# 03-LcdSegment.net
KiCad netlist of a schematic drawn in Altium Designer
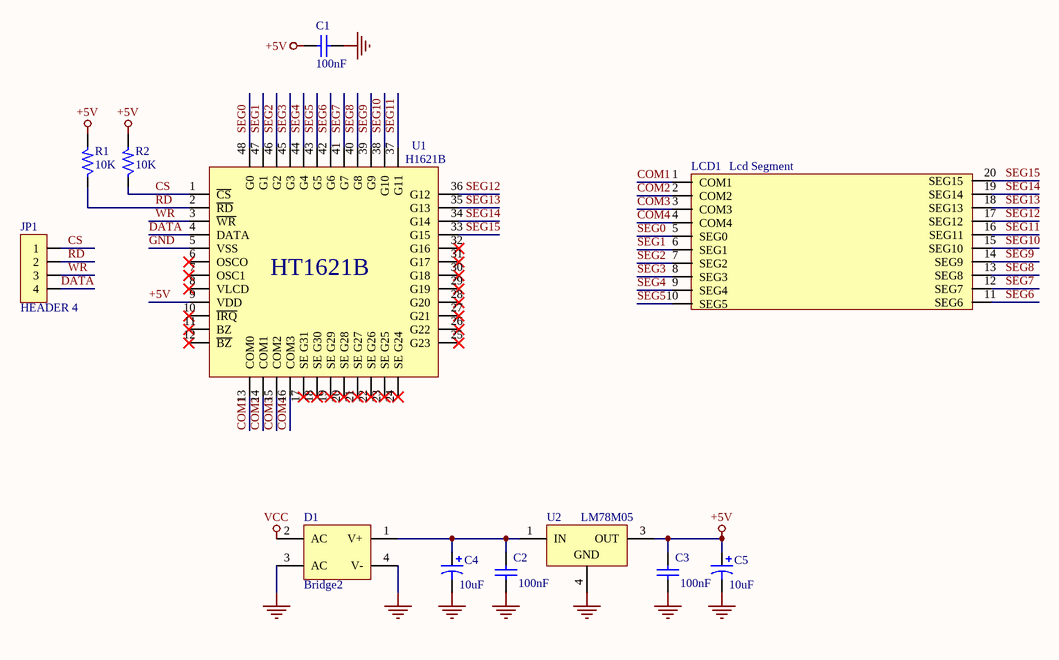
[diagram p0: 03-LcdSegment.SchDoc]

(export (version "E")
  (design (tool "Eeschema 10.0.6"))
  (components
    (comp (ref "C1")
      (value "100nF")
      (footprint "RAD-0.3")
      (description "Capacitor")
      (fields (field (name "Comment") "104") (field (name "PUBLISHER") "Altium Limited"))
      (libsource (lib "Miscellaneous Devices") (part "Cap"))
    )
    (comp (ref "C2")
      (value "100nF")
      (footprint "RAD-0.3")
      (description "Capacitor")
      (fields (field (name "Comment") "104") (field (name "PUBLISHER") "Altium Limited"))
      (libsource (lib "Miscellaneous Devices") (part "Cap"))
    )
    (comp (ref "C3")
      (value "100nF")
      (footprint "RAD-0.3")
      (description "Capacitor")
      (fields (field (name "Comment") "104") (field (name "PUBLISHER") "Altium Limited"))
      (libsource (lib "Miscellaneous Devices") (part "Cap"))
    )
    (comp (ref "C4")
      (value "10uF")
      (footprint "RB7.6-15")
      (description "Polarized Capacitor (Radial)")
      (fields (field (name "Comment") "10uF/16V") (field (name "PUBLISHER") "Altium Limited"))
      (libsource (lib "Miscellaneous Devices") (part "Cap Pol1"))
    )
    (comp (ref "C5")
      (value "10uF")
      (footprint "RB7.6-15")
      (description "Polarized Capacitor (Radial)")
      (fields (field (name "Comment") "10uF/16V") (field (name "PUBLISHER") "Altium Limited"))
      (libsource (lib "Miscellaneous Devices") (part "Cap Pol1"))
    )
    (comp (ref "D1")
      (value "Bridge2")
      (footprint "D-46_6A")
      (description "Diode Bridge")
      (fields (field (name "PUBLISHER") "Altium Limited"))
      (libsource (lib "Miscellaneous Devices") (part "Bridge2"))
    )
    (comp (ref "JP1")
      (value "HEADER 4")
      (footprint "JP4-C1T")
      (description "WR-PHD 2.54 mm Angled Socket Header")
      (fields
        (field (name "MANUFACTURER") "Würth Elektronik eiSos GmbH")
        (field (name "PARTNO") "613004143121")
        (field (name "CREATED BY") "Karrer Zheng")
      )
      (libsource (lib "LIBRARY") (part "JP4"))
    )
    (comp (ref "LCD1")
      (value "Lcd Segment")
      (footprint "LCD_SEG_6")
      (libsource (lib "MrQuan") (part "LCD_SEG"))
    )
    (comp (ref "R1") (value "10K") (footprint "RES-0805") (libsource (lib "MrQuan") (part "Res1/4W")))
    (comp (ref "R2") (value "10K") (footprint "RES-0805") (libsource (lib "MrQuan") (part "Res1/4W")))
    (comp (ref "U1") (value "H1621B") (footprint "LQFP-48") (libsource (lib "MrQuan") (part "H1621B")))
    (comp (ref "U2")
      (value "LM78M05")
      (footprint "NDP0003B_M")
      (description "3-Terminal Positive Voltage Regulators, 3-pin TO-252")
      (fields (field (name "MANUFACTURER") "Texas Instruments") (field (name "Comment") "LM78M05CDTX"))
      (libsource (lib "Altium Content Vault") (part "CMP-0062-00204-3"))
    )
  )
  (nets
    (net (code "1") (name "+5V") (class "Default")
      (node (ref "C1") (pin "1") (pinfunction "1_1") (pintype "passive"))
      (node (ref "C3") (pin "1") (pinfunction "1_1") (pintype "passive"))
      (node (ref "C5") (pin "1") (pinfunction "1_1") (pintype "passive"))
      (node (ref "R1") (pin "2") (pinfunction "2_2") (pintype "passive"))
      (node (ref "R2") (pin "2") (pinfunction "2_2") (pintype "passive"))
      (node (ref "U1") (pin "9") (pinfunction "VDD_9") (pintype "passive"))
      (node (ref "U2") (pin "3") (pinfunction "OUT_3") (pintype "power_in"))
    )
    (net (code "2") (name "/COM1") (class "Default")
      (node (ref "LCD1") (pin "1") (pinfunction "COM1_1") (pintype "passive"))
      (node (ref "U1") (pin "13") (pinfunction "COM0_13") (pintype "passive"))
    )
    (net (code "3") (name "/COM2") (class "Default")
      (node (ref "LCD1") (pin "2") (pinfunction "COM2_2") (pintype "passive"))
      (node (ref "U1") (pin "14") (pinfunction "COM1_14") (pintype "passive"))
    )
    (net (code "4") (name "/COM3") (class "Default")
      (node (ref "LCD1") (pin "3") (pinfunction "COM3_3") (pintype "passive"))
      (node (ref "U1") (pin "15") (pinfunction "COM2_15") (pintype "passive"))
    )
    (net (code "5") (name "/COM4") (class "Default")
      (node (ref "LCD1") (pin "4") (pinfunction "COM4_4") (pintype "passive"))
      (node (ref "U1") (pin "16") (pinfunction "COM3_16") (pintype "passive"))
    )
    (net (code "6") (name "/CS") (class "Default")
      (node (ref "JP1") (pin "1") (pinfunction "1_1") (pintype "passive"))
      (node (ref "R2") (pin "1") (pinfunction "1_1") (pintype "passive"))
      (node (ref "U1") (pin "1") (pinfunction "~{CS}_1") (pintype "passive"))
    )
    (net (code "7") (name "/DATA") (class "Default")
      (node (ref "JP1") (pin "4") (pinfunction "4_4") (pintype "passive"))
      (node (ref "U1") (pin "4") (pinfunction "DATA_4") (pintype "passive"))
    )
    (net (code "8") (name "/RD") (class "Default")
      (node (ref "JP1") (pin "2") (pinfunction "2_2") (pintype "passive"))
      (node (ref "R1") (pin "1") (pinfunction "1_1") (pintype "passive"))
      (node (ref "U1") (pin "2") (pinfunction "~{RD}_2") (pintype "passive"))
    )
    (net (code "9") (name "/SEG0") (class "Default")
      (node (ref "LCD1") (pin "5") (pinfunction "SEG0_5") (pintype "passive"))
      (node (ref "U1") (pin "48") (pinfunction "G0_48") (pintype "passive"))
    )
    (net (code "10") (name "/SEG1") (class "Default")
      (node (ref "LCD1") (pin "6") (pinfunction "SEG1_6") (pintype "passive"))
      (node (ref "U1") (pin "47") (pinfunction "G1_47") (pintype "passive"))
    )
    (net (code "11") (name "/SEG2") (class "Default")
      (node (ref "LCD1") (pin "7") (pinfunction "SEG2_7") (pintype "passive"))
      (node (ref "U1") (pin "46") (pinfunction "G2_46") (pintype "passive"))
    )
    (net (code "12") (name "/SEG3") (class "Default")
      (node (ref "LCD1") (pin "8") (pinfunction "SEG3_8") (pintype "passive"))
      (node (ref "U1") (pin "45") (pinfunction "G3_45") (pintype "passive"))
    )
    (net (code "13") (name "/SEG4") (class "Default")
      (node (ref "LCD1") (pin "9") (pinfunction "SEG4_9") (pintype "passive"))
      (node (ref "U1") (pin "44") (pinfunction "G4_44") (pintype "passive"))
    )
    (net (code "14") (name "/SEG5") (class "Default")
      (node (ref "LCD1") (pin "10") (pinfunction "SEG5_10") (pintype "passive"))
      (node (ref "U1") (pin "43") (pinfunction "G5_43") (pintype "passive"))
    )
    (net (code "15") (name "/SEG6") (class "Default")
      (node (ref "LCD1") (pin "11") (pinfunction "SEG6_11") (pintype "passive"))
      (node (ref "U1") (pin "42") (pinfunction "G6_42") (pintype "passive"))
    )
    (net (code "16") (name "/SEG7") (class "Default")
      (node (ref "LCD1") (pin "12") (pinfunction "SEG7_12") (pintype "passive"))
      (node (ref "U1") (pin "41") (pinfunction "G7_41") (pintype "passive"))
    )
    (net (code "17") (name "/SEG8") (class "Default")
      (node (ref "LCD1") (pin "13") (pinfunction "SEG8_13") (pintype "passive"))
      (node (ref "U1") (pin "40") (pinfunction "G8_40") (pintype "passive"))
    )
    (net (code "18") (name "/SEG9") (class "Default")
      (node (ref "LCD1") (pin "14") (pinfunction "SEG9_14") (pintype "passive"))
      (node (ref "U1") (pin "39") (pinfunction "G9_39") (pintype "passive"))
    )
    (net (code "19") (name "/SEG10") (class "Default")
      (node (ref "LCD1") (pin "15") (pinfunction "SEG10_15") (pintype "passive"))
      (node (ref "U1") (pin "38") (pinfunction "G10_38") (pintype "passive"))
    )
    (net (code "20") (name "/SEG11") (class "Default")
      (node (ref "LCD1") (pin "16") (pinfunction "SEG11_16") (pintype "passive"))
      (node (ref "U1") (pin "37") (pinfunction "G11_37") (pintype "passive"))
    )
    (net (code "21") (name "/SEG12") (class "Default")
      (node (ref "LCD1") (pin "17") (pinfunction "SEG12_17") (pintype "passive"))
      (node (ref "U1") (pin "36") (pinfunction "G12_36") (pintype "passive"))
    )
    (net (code "22") (name "/SEG13") (class "Default")
      (node (ref "LCD1") (pin "18") (pinfunction "SEG13_18") (pintype "passive"))
      (node (ref "U1") (pin "35") (pinfunction "G13_35") (pintype "passive"))
    )
    (net (code "23") (name "/SEG14") (class "Default")
      (node (ref "LCD1") (pin "19") (pinfunction "SEG14_19") (pintype "passive"))
      (node (ref "U1") (pin "34") (pinfunction "G14_34") (pintype "passive"))
    )
    (net (code "24") (name "/SEG15") (class "Default")
      (node (ref "LCD1") (pin "20") (pinfunction "SEG15_20") (pintype "passive"))
      (node (ref "U1") (pin "33") (pinfunction "G15_33") (pintype "passive"))
    )
    (net (code "25") (name "/WR") (class "Default")
      (node (ref "JP1") (pin "3") (pinfunction "3_3") (pintype "passive"))
      (node (ref "U1") (pin "3") (pinfunction "~{WR}_3") (pintype "passive"))
    )
    (net (code "26") (name "GND") (class "Default")
      (node (ref "C1") (pin "2") (pinfunction "2_2") (pintype "passive"))
      (node (ref "C2") (pin "2") (pinfunction "2_2") (pintype "passive"))
      (node (ref "C3") (pin "2") (pinfunction "2_2") (pintype "passive"))
      (node (ref "C4") (pin "2") (pinfunction "2_2") (pintype "passive"))
      (node (ref "C5") (pin "2") (pinfunction "2_2") (pintype "passive"))
      (node (ref "D1") (pin "3") (pinfunction "AC_3") (pintype "passive"))
      (node (ref "D1") (pin "4") (pinfunction "V-_4") (pintype "passive"))
      (node (ref "U1") (pin "5") (pinfunction "VSS_5") (pintype "passive"))
      (node (ref "U2") (pin "4") (pinfunction "GND_4") (pintype "power_in"))
    )
    (net (code "27") (name "Net-(D1-V+)") (class "Default")
      (node (ref "C2") (pin "1") (pinfunction "1_1") (pintype "passive"))
      (node (ref "C4") (pin "1") (pinfunction "1_1") (pintype "passive"))
      (node (ref "D1") (pin "1") (pinfunction "V+_1") (pintype "passive"))
      (node (ref "U2") (pin "1") (pinfunction "IN_1") (pintype "power_in"))
    )
    (net (code "28") (name "VCC") (class "Default")
      (node (ref "D1") (pin "2") (pinfunction "AC_2") (pintype "passive"))
    )
    (net (code "29") (name "unconnected-(U1-BZ-Pad11)") (class "Default")
      (node (ref "U1") (pin "11") (pinfunction "BZ_11") (pintype "passive+no_connect"))
    )
    (net (code "30") (name "unconnected-(U1-G16-Pad32)") (class "Default")
      (node (ref "U1") (pin "32") (pinfunction "G16_32") (pintype "passive+no_connect"))
    )
    (net (code "31") (name "unconnected-(U1-G17-Pad31)") (class "Default")
      (node (ref "U1") (pin "31") (pinfunction "G17_31") (pintype "passive+no_connect"))
    )
    (net (code "32") (name "unconnected-(U1-G18-Pad30)") (class "Default")
      (node (ref "U1") (pin "30") (pinfunction "G18_30") (pintype "passive+no_connect"))
    )
    (net (code "33") (name "unconnected-(U1-G19-Pad29)") (class "Default")
      (node (ref "U1") (pin "29") (pinfunction "G19_29") (pintype "passive+no_connect"))
    )
    (net (code "34") (name "unconnected-(U1-G20-Pad28)") (class "Default")
      (node (ref "U1") (pin "28") (pinfunction "G20_28") (pintype "passive+no_connect"))
    )
    (net (code "35") (name "unconnected-(U1-G21-Pad27)") (class "Default")
      (node (ref "U1") (pin "27") (pinfunction "G21_27") (pintype "passive+no_connect"))
    )
    (net (code "36") (name "unconnected-(U1-G22-Pad26)") (class "Default")
      (node (ref "U1") (pin "26") (pinfunction "G22_26") (pintype "passive+no_connect"))
    )
    (net (code "37") (name "unconnected-(U1-G23-Pad25)") (class "Default")
      (node (ref "U1") (pin "25") (pinfunction "G23_25") (pintype "passive+no_connect"))
    )
    (net (code "38") (name "unconnected-(U1-OSC1-Pad7)") (class "Default")
      (node (ref "U1") (pin "7") (pinfunction "OSC1_7") (pintype "passive+no_connect"))
    )
    (net (code "39") (name "unconnected-(U1-OSCO-Pad6)") (class "Default")
      (node (ref "U1") (pin "6") (pinfunction "OSCO_6") (pintype "passive+no_connect"))
    )
    (net (code "40") (name "unconnected-(U1-SE_G24-Pad24)") (class "Default")
      (node (ref "U1") (pin "24") (pinfunction "SE_G24_24") (pintype "passive+no_connect"))
    )
    (net (code "41") (name "unconnected-(U1-SE_G25-Pad23)") (class "Default")
      (node (ref "U1") (pin "23") (pinfunction "SE_G25_23") (pintype "passive+no_connect"))
    )
    (net (code "42") (name "unconnected-(U1-SE_G26-Pad22)") (class "Default")
      (node (ref "U1") (pin "22") (pinfunction "SE_G26_22") (pintype "passive+no_connect"))
    )
    (net (code "43") (name "unconnected-(U1-SE_G27-Pad21)") (class "Default")
      (node (ref "U1") (pin "21") (pinfunction "SE_G27_21") (pintype "passive+no_connect"))
    )
    (net (code "44") (name "unconnected-(U1-SE_G28-Pad20)") (class "Default")
      (node (ref "U1") (pin "20") (pinfunction "SE_G28_20") (pintype "passive+no_connect"))
    )
    (net (code "45") (name "unconnected-(U1-SE_G29-Pad19)") (class "Default")
      (node (ref "U1") (pin "19") (pinfunction "SE_G29_19") (pintype "passive+no_connect"))
    )
    (net (code "46") (name "unconnected-(U1-SE_G30-Pad18)") (class "Default")
      (node (ref "U1") (pin "18") (pinfunction "SE_G30_18") (pintype "passive+no_connect"))
    )
    (net (code "47") (name "unconnected-(U1-SE_G31-Pad17)") (class "Default")
      (node (ref "U1") (pin "17") (pinfunction "SE_G31_17") (pintype "passive+no_connect"))
    )
    (net (code "48") (name "unconnected-(U1-VLCD-Pad8)") (class "Default")
      (node (ref "U1") (pin "8") (pinfunction "VLCD_8") (pintype "passive+no_connect"))
    )
    (net (code "49") (name "unconnected-(U1-~{BZ}-Pad12)") (class "Default")
      (node (ref "U1") (pin "12") (pinfunction "~{BZ}_12") (pintype "passive+no_connect"))
    )
    (net (code "50") (name "unconnected-(U1-~{IRQ}-Pad10)") (class "Default")
      (node (ref "U1") (pin "10") (pinfunction "~{IRQ}_10") (pintype "passive+no_connect"))
    )
  )
)
